# P05_PWM-DAC.net
KiCad netlist of a schematic drawn in Altium Designer
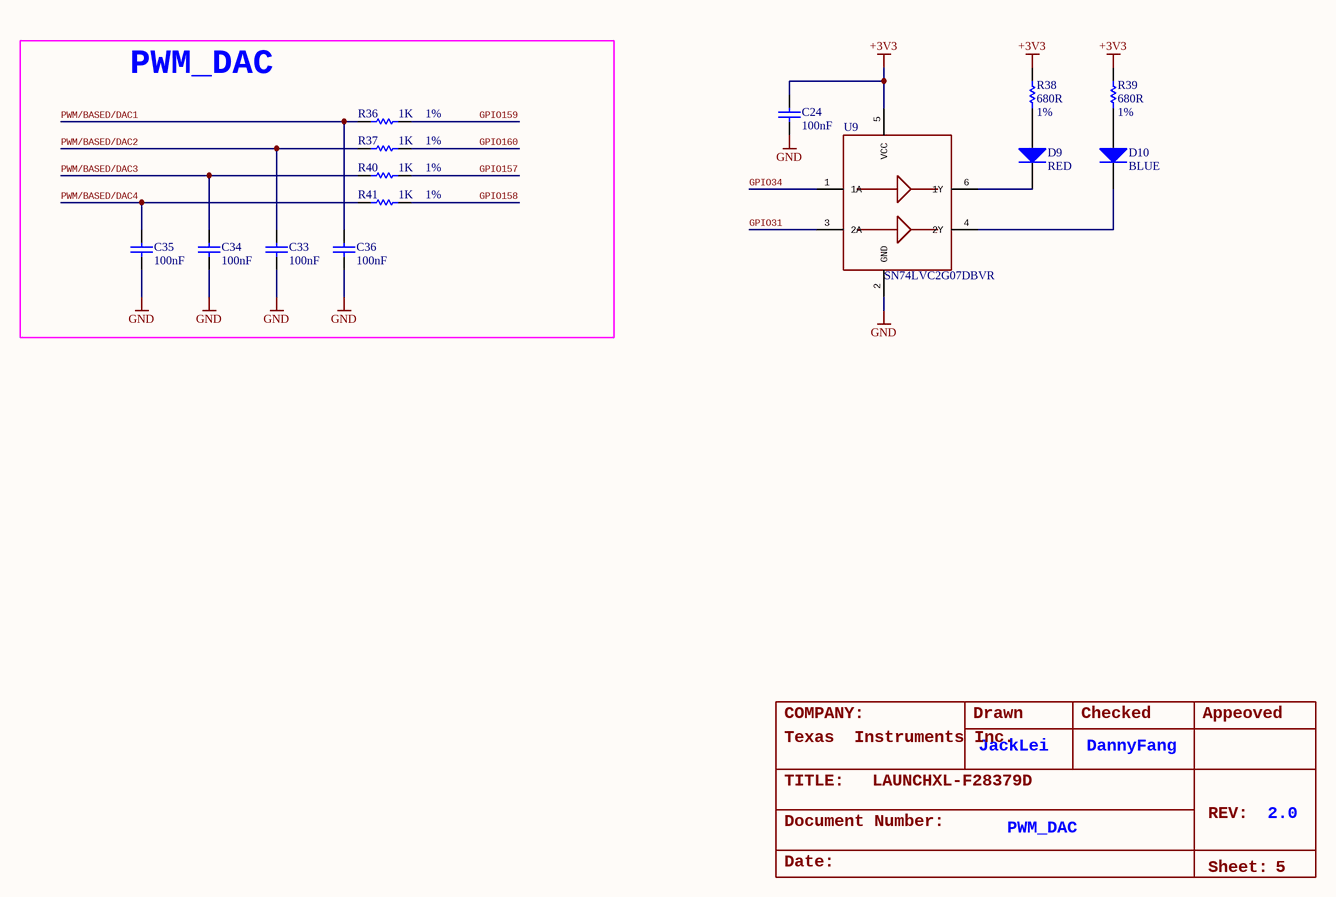
[diagram p0: P05_PWM-DAC.SchDoc]

(export (version "E")
  (design (tool "Eeschema 10.0.6"))
  (components
    (comp (ref "C24")
      (value "100nF")
      (footprint "C0402")
      (description "CAP,100NF(0.1uf),+/-10%,X5R,10V,SMD0402")
      (fields
        (field (name "MANUFACTURER") "MURATA")
        (field (name "MANUFACTURER PART NUMBER") "GRM155R61A104KA01D")
      )
      (libsource (lib "Embest") (part "C"))
    )
    (comp (ref "C33")
      (value "100nF")
      (footprint "C0402")
      (description "CAP,100NF(0.1uf),+/-10%,X5R,10V,SMD0402")
      (fields
        (field (name "MANUFACTURER") "MURATA")
        (field (name "MANUFACTURER PART NUMBER") "GRM155R61A104KA01D")
      )
      (libsource (lib "Embest") (part "C"))
    )
    (comp (ref "C34")
      (value "100nF")
      (footprint "C0402")
      (description "CAP,100NF(0.1uf),+/-10%,X5R,10V,SMD0402")
      (fields
        (field (name "MANUFACTURER") "MURATA")
        (field (name "MANUFACTURER PART NUMBER") "GRM155R61A104KA01D")
      )
      (libsource (lib "Embest") (part "C"))
    )
    (comp (ref "C35")
      (value "100nF")
      (footprint "C0402")
      (description "CAP,100NF(0.1uf),+/-10%,X5R,10V,SMD0402")
      (fields
        (field (name "MANUFACTURER") "MURATA")
        (field (name "MANUFACTURER PART NUMBER") "GRM155R61A104KA01D")
      )
      (libsource (lib "Embest") (part "C"))
    )
    (comp (ref "C36")
      (value "100nF")
      (footprint "C0402")
      (description "CAP,100NF(0.1uf),+/-10%,X5R,10V,SMD0402")
      (fields
        (field (name "MANUFACTURER") "MURATA")
        (field (name "MANUFACTURER PART NUMBER") "GRM155R61A104KA01D")
      )
      (libsource (lib "Embest") (part "C"))
    )
    (comp (ref "D9")
      (value "RED")
      (footprint "D0805")
      (description "LED, SUPPER RED ,630NM,30mA, SMD,0805")
      (fields (field (name "MANUFACTURER") "WURTH") (field (name "MANUFACTURER PART NUMBER") "150080SS75000"))
      (libsource (lib "Embest") (part "D"))
    )
    (comp (ref "D10")
      (value "BLUE")
      (footprint "D0805")
      (description "LED, BLUE ,470NM, 30mA,SMD,0805")
      (fields (field (name "MANUFACTURER") "WURTH") (field (name "MANUFACTURER PART NUMBER") "150080BS75000"))
      (libsource (lib "Embest") (part "D"))
    )
    (comp (ref "R36")
      (value "1K")
      (footprint "R0402")
      (description "RES,1K,+/-1%,1/16W,SMD0402")
      (fields
        (field (name "RATING") "1%")
        (field (name "MANUFACTURER") "YAGEO")
        (field (name "MANUFACTURER PART NUMBER") "RC0402FR-071KL")
      )
      (libsource (lib "Embest") (part "R"))
    )
    (comp (ref "R37")
      (value "1K")
      (footprint "R0402")
      (description "RES,1K,+/-1%,1/16W,SMD0402")
      (fields
        (field (name "RATING") "1%")
        (field (name "MANUFACTURER") "YAGEO")
        (field (name "MANUFACTURER PART NUMBER") "RC0402FR-071KL")
      )
      (libsource (lib "Embest") (part "R"))
    )
    (comp (ref "R38")
      (value "680R")
      (footprint "R0402")
      (description "RES,680R,+/-1%,1/16W,SMD0402")
      (fields
        (field (name "RATING") "1%")
        (field (name "MANUFACTURER") "YAGEO")
        (field (name "MANUFACTURER PART NUMBER") "RC0402FR-07680RL")
      )
      (libsource (lib "Embest") (part "R"))
    )
    (comp (ref "R39")
      (value "680R")
      (footprint "R0402")
      (description "RES,680R,+/-1%,1/16W,SMD0402")
      (fields
        (field (name "RATING") "1%")
        (field (name "MANUFACTURER") "YAGEO")
        (field (name "MANUFACTURER PART NUMBER") "RC0402FR-07680RL")
      )
      (libsource (lib "Embest") (part "R"))
    )
    (comp (ref "R40")
      (value "1K")
      (footprint "R0402")
      (description "RES,1K,+/-1%,1/16W,SMD0402")
      (fields
        (field (name "RATING") "1%")
        (field (name "MANUFACTURER") "YAGEO")
        (field (name "MANUFACTURER PART NUMBER") "RC0402FR-071KL")
      )
      (libsource (lib "Embest") (part "R"))
    )
    (comp (ref "R41")
      (value "1K")
      (footprint "R0402")
      (description "RES,1K,+/-1%,1/16W,SMD0402")
      (fields
        (field (name "RATING") "1%")
        (field (name "MANUFACTURER") "YAGEO")
        (field (name "MANUFACTURER PART NUMBER") "RC0402FR-071KL")
      )
      (libsource (lib "Embest") (part "R"))
    )
    (comp (ref "U9")
      (value "SN74LVC2G07DBVR")
      (footprint "SOT23-6")
      (description "Buffer/Driver 2-CH Non-Inverting Open Drain CMOS 6-Pin SOT-23 T/R,CUSTOMER SUPPLY")
      (fields (field (name "MANUFACTURER") "TI"))
      (libsource (lib "Embest") (part "SN74LVC2G07"))
    )
  )
  (nets
    (net (code "1") (name "+3V3") (class "Default")
      (node (ref "C24") (pin "2") (pinfunction "2_2") (pintype "passive"))
      (node (ref "R38") (pin "2") (pinfunction "2_2") (pintype "passive"))
      (node (ref "R39") (pin "2") (pinfunction "2_2") (pintype "passive"))
      (node (ref "U9") (pin "5") (pinfunction "VCC_5") (pintype "passive"))
    )
    (net (code "2") (name "/GPIO31") (class "Default")
      (node (ref "U9") (pin "3") (pinfunction "2A_3") (pintype "passive"))
    )
    (net (code "3") (name "/GPIO34") (class "Default")
      (node (ref "U9") (pin "1") (pinfunction "1A_1") (pintype "passive"))
    )
    (net (code "4") (name "/GPIO157") (class "Default")
      (node (ref "R40") (pin "1") (pinfunction "1_1") (pintype "passive"))
    )
    (net (code "5") (name "/GPIO158") (class "Default")
      (node (ref "R41") (pin "1") (pinfunction "1_1") (pintype "passive"))
    )
    (net (code "6") (name "/GPIO159") (class "Default")
      (node (ref "R36") (pin "1") (pinfunction "1_1") (pintype "passive"))
    )
    (net (code "7") (name "/GPIO160") (class "Default")
      (node (ref "R37") (pin "1") (pinfunction "1_1") (pintype "passive"))
    )
    (net (code "8") (name "/PWM{slash}BASED{slash}DAC1") (class "Default")
      (node (ref "C36") (pin "2") (pinfunction "2_2") (pintype "passive"))
      (node (ref "R36") (pin "2") (pinfunction "2_2") (pintype "passive"))
    )
    (net (code "9") (name "/PWM{slash}BASED{slash}DAC2") (class "Default")
      (node (ref "C33") (pin "2") (pinfunction "2_2") (pintype "passive"))
      (node (ref "R37") (pin "2") (pinfunction "2_2") (pintype "passive"))
    )
    (net (code "10") (name "/PWM{slash}BASED{slash}DAC3") (class "Default")
      (node (ref "C34") (pin "2") (pinfunction "2_2") (pintype "passive"))
      (node (ref "R40") (pin "2") (pinfunction "2_2") (pintype "passive"))
    )
    (net (code "11") (name "/PWM{slash}BASED{slash}DAC4") (class "Default")
      (node (ref "C35") (pin "2") (pinfunction "2_2") (pintype "passive"))
      (node (ref "R41") (pin "2") (pinfunction "2_2") (pintype "passive"))
    )
    (net (code "12") (name "GND") (class "Default")
      (node (ref "C24") (pin "1") (pinfunction "1_1") (pintype "passive"))
      (node (ref "C33") (pin "1") (pinfunction "1_1") (pintype "passive"))
      (node (ref "C34") (pin "1") (pinfunction "1_1") (pintype "passive"))
      (node (ref "C35") (pin "1") (pinfunction "1_1") (pintype "passive"))
      (node (ref "C36") (pin "1") (pinfunction "1_1") (pintype "passive"))
      (node (ref "U9") (pin "2") (pinfunction "GND_2") (pintype "passive"))
    )
    (net (code "13") (name "Net-(D9-Pad2)") (class "Default")
      (node (ref "D9") (pin "2") (pinfunction "2_2") (pintype "passive"))
      (node (ref "R38") (pin "1") (pinfunction "1_1") (pintype "passive"))
    )
    (net (code "14") (name "Net-(D10-Pad2)") (class "Default")
      (node (ref "D10") (pin "2") (pinfunction "2_2") (pintype "passive"))
      (node (ref "R39") (pin "1") (pinfunction "1_1") (pintype "passive"))
    )
    (net (code "15") (name "Net-(U9-1Y)") (class "Default")
      (node (ref "D9") (pin "1") (pinfunction "1_1") (pintype "passive"))
      (node (ref "U9") (pin "6") (pinfunction "1Y_6") (pintype "passive"))
    )
    (net (code "16") (name "Net-(U9-2Y)") (class "Default")
      (node (ref "D10") (pin "1") (pinfunction "1_1") (pintype "passive"))
      (node (ref "U9") (pin "4") (pinfunction "2Y_4") (pintype "passive"))
    )
  )
)
